# Battery_3.net
KiCad netlist of a schematic drawn in Altium Designer
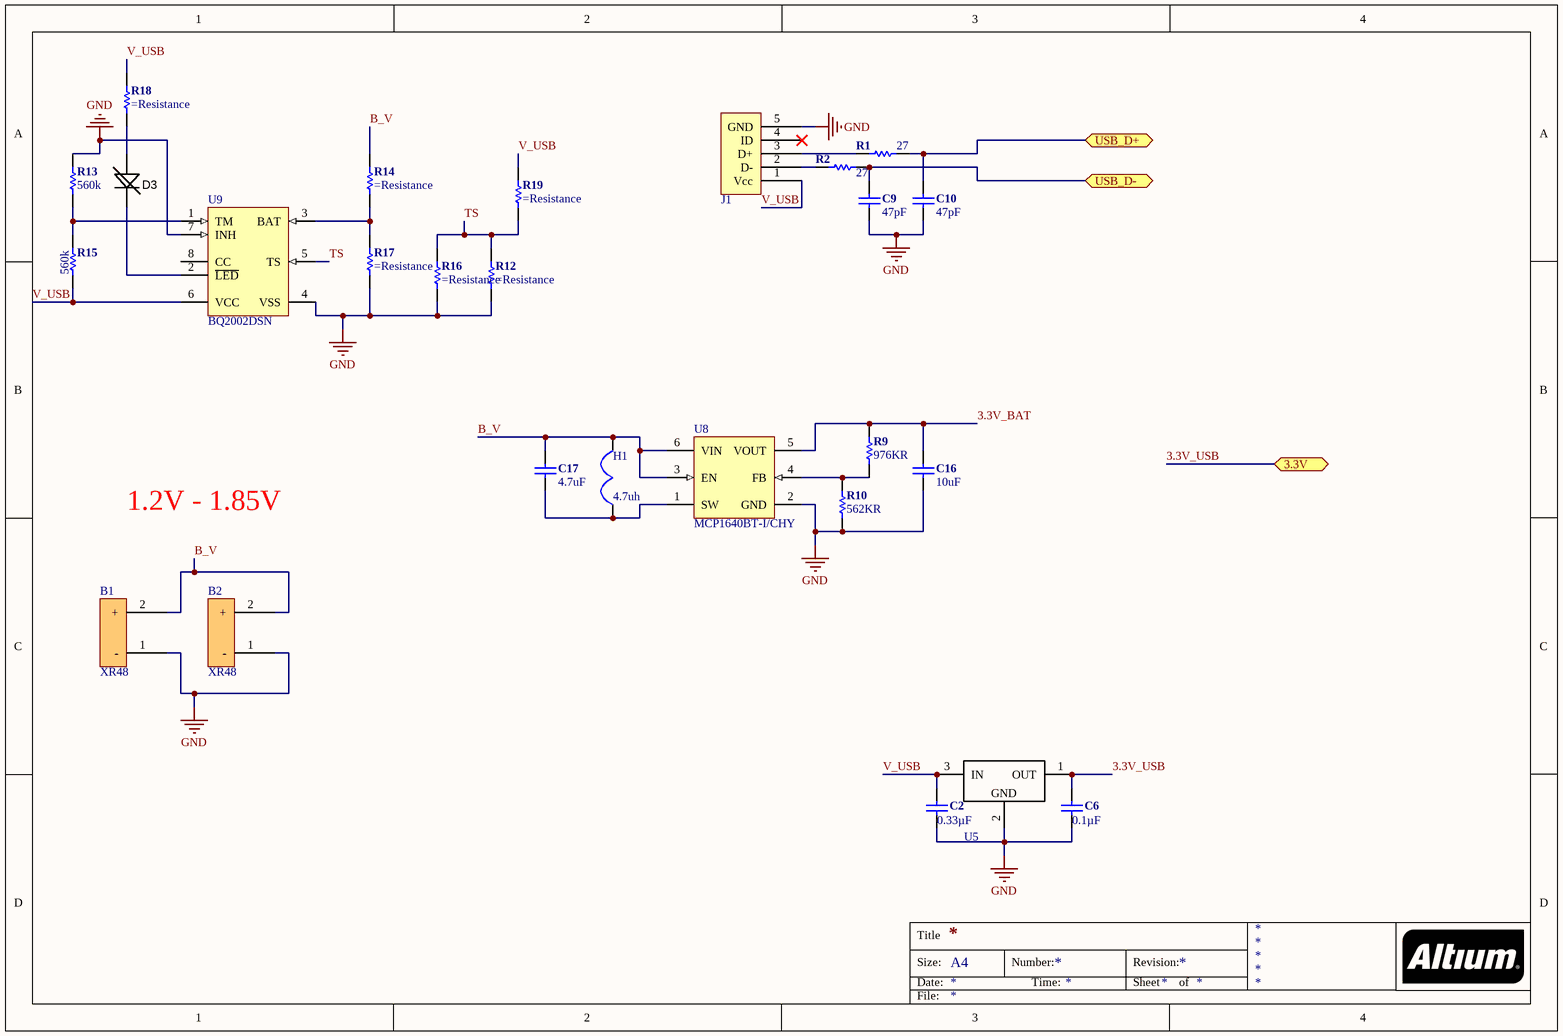
[diagram p0: Battery_3.SchDoc]

(export (version "E")
  (design (tool "Eeschema 10.0.6"))
  (components
    (comp (ref "B1") (value "XR48") (footprint "XR48") (libsource (lib "Glove") (part "XR48")))
    (comp (ref "B2") (value "XR48") (footprint "XR48") (libsource (lib "Glove") (part "XR48")))
    (comp (ref "C2")
      (value "0.33µF")
      (footprint "CAP-0805(2012)-R")
      (description "___ OHM ___ mW 0805(2012) SMD")
      (fields
        (field (name "MANUFACTURER") "Yageo")
        (field (name "MANUFACTURER PART NUMBER") "CC0805KKX7R7BB334")
      )
      (libsource (lib "Glove") (part "C-0805(2012)"))
    )
    (comp (ref "C6")
      (value "0.1µF")
      (footprint "CAP-0805(2012)-R")
      (description "___ OHM ___ mW 0805(2012) SMD")
      (fields
        (field (name "MANUFACTURER") "Yageo")
        (field (name "MANUFACTURER PART NUMBER") "CC0805KRX7R9BB104")
      )
      (libsource (lib "Glove") (part "C-0805(2012)"))
    )
    (comp (ref "C9")
      (value "47pF")
      (footprint "CAP-0805(2012)-R")
      (description "___ OHM ___ mW 0805(2012) SMD")
      (fields
        (field (name "MANUFACTURER") "Yageo")
        (field (name "MANUFACTURER PART NUMBER") "CC0805JRNPO9BN470")
      )
      (libsource (lib "Glove") (part "C-0805(2012)"))
    )
    (comp (ref "C10")
      (value "47pF")
      (footprint "CAP-0805(2012)-R")
      (description "___ OHM ___ mW 0805(2012) SMD")
      (fields
        (field (name "MANUFACTURER") "Yageo")
        (field (name "MANUFACTURER PART NUMBER") "CC0805JRNPO9BN470")
      )
      (libsource (lib "Glove") (part "C-0805(2012)"))
    )
    (comp (ref "C16")
      (value "10uF")
      (footprint "CAP-0805(2012)-R")
      (description "___ OHM ___ mW 0805(2012) SMD")
      (fields
        (field (name "MANUFACTURER") "Murata")
        (field (name "MANUFACTURER PART NUMBER") "GRM219R61A106KE44D")
      )
      (libsource (lib "Glove") (part "C-0805(2012)"))
    )
    (comp (ref "C17")
      (value "4.7uF")
      (footprint "CAP-0805(2012)-R")
      (description "___ OHM ___ mW 0805(2012) SMD")
      (fields
        (field (name "MANUFACTURER") "Murata")
        (field (name "MANUFACTURER PART NUMBER") "GRM21BR61C475KA88L")
      )
      (libsource (lib "Glove") (part "C-0805(2012)"))
    )
    (comp (ref "D3")
      (value "Red")
      (footprint "LED-0805-A")
      (description "LED, 0805 SMD, Red")
      (fields
        (field (name "MANUFACTURER") "OSRAM Opto Semiconductors Inc.")
        (field (name "MANUFACTURER PART NUMBER") "LS R976-NR-1")
      )
      (libsource (lib "Glove") (part "LED_0805_RED"))
    )
    (comp (ref "H1")
      (value "H-0805(2012)")
      (footprint "H-0805(2012)-H")
      (description "FIXED IND 4.7UH 700MA 260 MOHM")
      (fields
        (field (name "MANUFACTURER") "TDK")
        (field (name "MANUFACTURER PART NUMBER") "MLP2012S4R7MT0S1")
        (field (name "INDUCTANCE") "4.7uh")
      )
      (libsource (lib "Glove") (part "H-0805(2012)"))
    )
    (comp (ref "J1")
      (value "USB")
      (footprint "USB_Connector_5P_MICRO_USB_FCI")
      (description "USB_Connector_5P_MICRO_USB_FCI")
      (fields
        (field (name "MANUFACTURER") "Amphenol FCI")
        (field (name "MANUFACTURER PART NUMBER") "10118194-0001LF")
      )
      (libsource (lib "Glove") (part "USB"))
    )
    (comp (ref "R1")
      (value "27")
      (footprint "R-0805(2012)-R")
      (description "___ OHM ___ mW 0805(2012) SMD")
      (fields
        (field (name "MANUFACTURER") "Yageo")
        (field (name "MANUFACTURER PART NUMBER") "RC0805JR-0727RL")
      )
      (libsource (lib "Glove") (part "R-0805(2012)"))
    )
    (comp (ref "R2")
      (value "27")
      (footprint "R-0805(2012)-R")
      (description "___ OHM ___ mW 0805(2012) SMD")
      (fields
        (field (name "MANUFACTURER") "Yageo")
        (field (name "MANUFACTURER PART NUMBER") "RC0805JR-0727RL")
      )
      (libsource (lib "Glove") (part "R-0805(2012)"))
    )
    (comp (ref "R9")
      (value "976KR")
      (footprint "R-0805(2012)-R")
      (description "___ OHM ___ mW 0805(2012) SMD")
      (fields
        (field (name "MANUFACTURER") "Panasonic ECG")
        (field (name "MANUFACTURER PART NUMBER") "ERJ-6ENF9763V")
      )
      (libsource (lib "Glove") (part "R-0805(2012)"))
    )
    (comp (ref "R10")
      (value "562KR")
      (footprint "R-0805(2012)-R")
      (description "___ OHM ___ mW 0805(2012) SMD")
      (fields
        (field (name "MANUFACTURER") "Vishay")
        (field (name "MANUFACTURER PART NUMBER") "CRCW0805562KFKEA")
      )
      (libsource (lib "Glove") (part "R-0805(2012)"))
    )
    (comp (ref "R12")
      (value "~")
      (footprint "R-0805(2012)-R")
      (description "___ OHM ___ mW 0805(2012) SMD")
      (libsource (lib "Glove") (part "R-0805(2012)"))
    )
    (comp (ref "R13")
      (value "560k")
      (footprint "R-0805(2012)-R")
      (description "___ OHM ___ mW 0805(2012) SMD")
      (libsource (lib "Glove") (part "R-0805(2012)"))
    )
    (comp (ref "R14")
      (value "~")
      (footprint "R-0805(2012)-R")
      (description "___ OHM ___ mW 0805(2012) SMD")
      (libsource (lib "Glove") (part "R-0805(2012)"))
    )
    (comp (ref "R15")
      (value "560k")
      (footprint "R-0805(2012)-R")
      (description "___ OHM ___ mW 0805(2012) SMD")
      (libsource (lib "Glove") (part "R-0805(2012)"))
    )
    (comp (ref "R16")
      (value "~")
      (footprint "R-0805(2012)-R")
      (description "___ OHM ___ mW 0805(2012) SMD")
      (libsource (lib "Glove") (part "R-0805(2012)"))
    )
    (comp (ref "R17")
      (value "~")
      (footprint "R-0805(2012)-R")
      (description "___ OHM ___ mW 0805(2012) SMD")
      (libsource (lib "Glove") (part "R-0805(2012)"))
    )
    (comp (ref "R18")
      (value "~")
      (footprint "R-0805(2012)-R")
      (description "___ OHM ___ mW 0805(2012) SMD")
      (libsource (lib "Glove") (part "R-0805(2012)"))
    )
    (comp (ref "R19")
      (value "~")
      (footprint "R-0805(2012)-R")
      (description "___ OHM ___ mW 0805(2012) SMD")
      (libsource (lib "Glove") (part "R-0805(2012)"))
    )
    (comp (ref "U5")
      (value "L78L33ACUTR")
      (footprint "SOT89-3")
      (fields (field (name "MANUFACTURER") "STMicroelectronics"))
      (libsource (lib "Glove") (part "L78L33ACUTR"))
    )
    (comp (ref "U8")
      (value "MCP1640BT-I/CHY")
      (footprint "MCHP-SOT-23-CHY6_L")
      (description "IC REG BST ADJ 0.1A SYNC SOT23-6")
      (fields (field (name "MANUFACTURER") "Microchip"))
      (libsource (lib "Altium Content Vault") (part "CMP-0139-00285-1"))
    )
    (comp (ref "U9")
      (value "BQ2002DSN")
      (footprint "D0008A_L")
      (description "IC CONTROLLER FASTCHRGE 8-SOIC")
      (fields (field (name "MANUFACTURER") "Texas Instruments"))
      (libsource (lib "Altium Content Vault") (part "CMP-0321-00383-2"))
    )
  )
  (nets
    (net (code "1") (name "/3.3V_BAT") (class "Default")
      (node (ref "C16") (pin "1") (pinfunction "1_1") (pintype "passive"))
      (node (ref "R9") (pin "1") (pinfunction "1_1") (pintype "passive"))
      (node (ref "U8") (pin "5") (pinfunction "VOUT_5") (pintype "power_in"))
    )
    (net (code "2") (name "/3.3V_USB") (class "Default")
      (node (ref "C6") (pin "1") (pinfunction "1_1") (pintype "passive"))
      (node (ref "U5") (pin "1") (pinfunction "OUT_1") (pintype "power_in"))
    )
    (net (code "3") (name "/B_V") (class "Default")
      (node (ref "B1") (pin "2") (pinfunction "+_2") (pintype "passive"))
      (node (ref "B2") (pin "2") (pinfunction "+_2") (pintype "passive"))
      (node (ref "C17") (pin "1") (pinfunction "1_1") (pintype "passive"))
      (node (ref "H1") (pin "2") (pinfunction "2_2") (pintype "passive"))
      (node (ref "R14") (pin "1") (pinfunction "1_1") (pintype "passive"))
      (node (ref "U8") (pin "3") (pinfunction "EN_3") (pintype "input"))
      (node (ref "U8") (pin "6") (pinfunction "VIN_6") (pintype "power_in"))
    )
    (net (code "4") (name "/TS") (class "Default")
      (node (ref "R12") (pin "1") (pinfunction "1_1") (pintype "passive"))
      (node (ref "R16") (pin "1") (pinfunction "1_1") (pintype "passive"))
      (node (ref "R19") (pin "2") (pinfunction "2_2") (pintype "passive"))
      (node (ref "U9") (pin "5") (pinfunction "TS_5") (pintype "input"))
    )
    (net (code "5") (name "/USB_D+") (class "Default")
      (node (ref "C10") (pin "2") (pinfunction "2_2") (pintype "passive"))
      (node (ref "R1") (pin "2") (pinfunction "2_2") (pintype "passive"))
    )
    (net (code "6") (name "/USB_D-") (class "Default")
      (node (ref "C9") (pin "2") (pinfunction "2_2") (pintype "passive"))
      (node (ref "R2") (pin "2") (pinfunction "2_2") (pintype "passive"))
    )
    (net (code "7") (name "/V_USB") (class "Default")
      (node (ref "C2") (pin "1") (pinfunction "1_1") (pintype "passive"))
      (node (ref "J1") (pin "1") (pinfunction "Vcc_1") (pintype "passive"))
      (node (ref "R15") (pin "2") (pinfunction "2_2") (pintype "passive"))
      (node (ref "R18") (pin "1") (pinfunction "1_1") (pintype "passive"))
      (node (ref "R19") (pin "1") (pinfunction "1_1") (pintype "passive"))
      (node (ref "U5") (pin "3") (pinfunction "IN_3") (pintype "passive"))
      (node (ref "U9") (pin "6") (pinfunction "VCC_6") (pintype "power_in"))
    )
    (net (code "8") (name "GND") (class "Default")
      (node (ref "B1") (pin "1") (pinfunction "-_1") (pintype "passive"))
      (node (ref "B2") (pin "1") (pinfunction "-_1") (pintype "passive"))
      (node (ref "C10") (pin "1") (pinfunction "1_1") (pintype "passive"))
      (node (ref "C16") (pin "2") (pinfunction "2_2") (pintype "passive"))
      (node (ref "C2") (pin "2") (pinfunction "2_2") (pintype "passive"))
      (node (ref "C6") (pin "2") (pinfunction "2_2") (pintype "passive"))
      (node (ref "C9") (pin "1") (pinfunction "1_1") (pintype "passive"))
      (node (ref "J1") (pin "5") (pinfunction "GND_5") (pintype "passive"))
      (node (ref "R10") (pin "2") (pinfunction "2_2") (pintype "passive"))
      (node (ref "R12") (pin "2") (pinfunction "2_2") (pintype "passive"))
      (node (ref "R13") (pin "1") (pinfunction "1_1") (pintype "passive"))
      (node (ref "R16") (pin "2") (pinfunction "2_2") (pintype "passive"))
      (node (ref "R17") (pin "2") (pinfunction "2_2") (pintype "passive"))
      (node (ref "U5") (pin "2") (pinfunction "GND_2") (pintype "power_in"))
      (node (ref "U8") (pin "2") (pinfunction "GND_2") (pintype "power_in"))
      (node (ref "U9") (pin "4") (pinfunction "VSS_4") (pintype "power_in"))
      (node (ref "U9") (pin "7") (pinfunction "INH_7") (pintype "input"))
    )
    (net (code "9") (name "Net-(D3-PadA)") (class "Default")
      (node (ref "D3") (pin "A") (pinfunction "A_A") (pintype "passive"))
      (node (ref "R18") (pin "2") (pinfunction "2_2") (pintype "passive"))
    )
    (net (code "10") (name "Net-(J1-D+)") (class "Default")
      (node (ref "J1") (pin "3") (pinfunction "D+_3") (pintype "passive"))
      (node (ref "R1") (pin "1") (pinfunction "1_1") (pintype "passive"))
    )
    (net (code "11") (name "Net-(J1-D-)") (class "Default")
      (node (ref "J1") (pin "2") (pinfunction "D-_2") (pintype "passive"))
      (node (ref "R2") (pin "1") (pinfunction "1_1") (pintype "passive"))
    )
    (net (code "12") (name "Net-(U8-FB)") (class "Default")
      (node (ref "R10") (pin "1") (pinfunction "1_1") (pintype "passive"))
      (node (ref "R9") (pin "2") (pinfunction "2_2") (pintype "passive"))
      (node (ref "U8") (pin "4") (pinfunction "FB_4") (pintype "input"))
    )
    (net (code "13") (name "Net-(U8-SW)") (class "Default")
      (node (ref "C17") (pin "2") (pinfunction "2_2") (pintype "passive"))
      (node (ref "H1") (pin "1") (pinfunction "1_1") (pintype "passive"))
      (node (ref "U8") (pin "1") (pinfunction "SW_1") (pintype "power_in"))
    )
    (net (code "14") (name "Net-(U9-BAT)") (class "Default")
      (node (ref "R14") (pin "2") (pinfunction "2_2") (pintype "passive"))
      (node (ref "R17") (pin "1") (pinfunction "1_1") (pintype "passive"))
      (node (ref "U9") (pin "3") (pinfunction "BAT_3") (pintype "input"))
    )
    (net (code "15") (name "Net-(U9-TM)") (class "Default")
      (node (ref "R13") (pin "2") (pinfunction "2_2") (pintype "passive"))
      (node (ref "R15") (pin "1") (pinfunction "1_1") (pintype "passive"))
      (node (ref "U9") (pin "1") (pinfunction "TM_1") (pintype "input"))
    )
    (net (code "16") (name "Net-(U9-~{LED})") (class "Default")
      (node (ref "D3") (pin "K") (pinfunction "K_K") (pintype "passive"))
      (node (ref "U9") (pin "2") (pinfunction "~{LED}_2") (pintype "tri_state"))
    )
    (net (code "17") (name "unconnected-(J1-ID-Pad4)") (class "Default")
      (node (ref "J1") (pin "4") (pinfunction "ID_4") (pintype "passive+no_connect"))
    )
    (net (code "18") (name "unconnected-(U9-CC-Pad8)") (class "Default")
      (node (ref "U9") (pin "8") (pinfunction "CC_8") (pintype "tri_state"))
    )
  )
)
